# imp_match_v1_1.net
KiCad netlist of a schematic drawn in Altium Designer
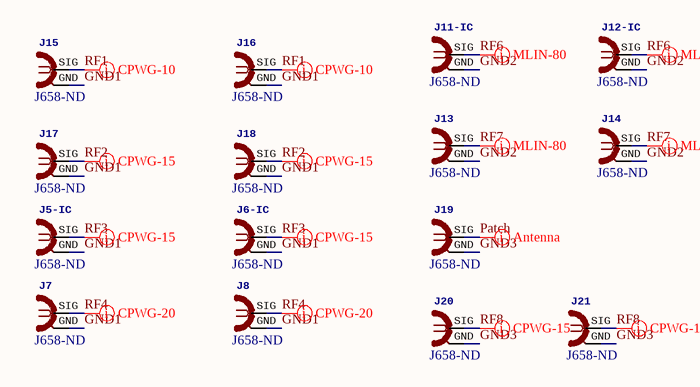
[diagram p0: imp_match_v1_1.SchDoc]

(export (version "E")
  (design (tool "Eeschema 10.0.6"))
  (components
    (comp (ref "J5-IC")
      (value "SMA 50 Ohm edge")
      (footprint "SMA-OSHPARK-4L-1.6MM- ALT3")
      (fields
        (field (name "SUPPLIER PART NUMBER 1") "J658-ND")
        (field (name "LIBRARYNAME") "dword1511-connectors")
      )
      (libsource (lib "wcsng_altium") (part "SMA-OSHPARK-4L-1.6MM-ALT3"))
    )
    (comp (ref "J6-IC")
      (value "SMA 50 Ohm edge")
      (footprint "SMA-OSHPARK-4L-1.6MM- ALT3")
      (fields
        (field (name "SUPPLIER PART NUMBER 1") "J658-ND")
        (field (name "LIBRARYNAME") "dword1511-connectors")
      )
      (libsource (lib "wcsng_altium") (part "SMA-OSHPARK-4L-1.6MM-ALT3"))
    )
    (comp (ref "J7")
      (value "SMA 50 Ohm edge")
      (footprint "SMA-OSHPARK-4L-1.6MM- ALT3")
      (fields
        (field (name "SUPPLIER PART NUMBER 1") "J658-ND")
        (field (name "LIBRARYNAME") "dword1511-connectors")
      )
      (libsource (lib "wcsng_altium") (part "SMA-OSHPARK-4L-1.6MM-ALT3"))
    )
    (comp (ref "J8")
      (value "SMA 50 Ohm edge")
      (footprint "SMA-OSHPARK-4L-1.6MM- ALT3")
      (fields
        (field (name "SUPPLIER PART NUMBER 1") "J658-ND")
        (field (name "LIBRARYNAME") "dword1511-connectors")
      )
      (libsource (lib "wcsng_altium") (part "SMA-OSHPARK-4L-1.6MM-ALT3"))
    )
    (comp (ref "J11-IC")
      (value "SMA 50 Ohm edge")
      (footprint "SMA-OSHPARK-4L-1.6MM- ALT3")
      (fields
        (field (name "SUPPLIER PART NUMBER 1") "J658-ND")
        (field (name "LIBRARYNAME") "dword1511-connectors")
      )
      (libsource (lib "wcsng_altium") (part "SMA-OSHPARK-4L-1.6MM-ALT3"))
    )
    (comp (ref "J12-IC")
      (value "SMA 50 Ohm edge")
      (footprint "SMA-OSHPARK-4L-1.6MM- ALT3")
      (fields
        (field (name "SUPPLIER PART NUMBER 1") "J658-ND")
        (field (name "LIBRARYNAME") "dword1511-connectors")
      )
      (libsource (lib "wcsng_altium") (part "SMA-OSHPARK-4L-1.6MM-ALT3"))
    )
    (comp (ref "J13")
      (value "SMA 50 Ohm edge")
      (footprint "SMA-OSHPARK-4L-1.6MM- ALT3")
      (fields
        (field (name "SUPPLIER PART NUMBER 1") "J658-ND")
        (field (name "LIBRARYNAME") "dword1511-connectors")
      )
      (libsource (lib "wcsng_altium") (part "SMA-OSHPARK-4L-1.6MM-ALT3"))
    )
    (comp (ref "J14")
      (value "SMA 50 Ohm edge")
      (footprint "SMA-OSHPARK-4L-1.6MM- ALT3")
      (fields
        (field (name "SUPPLIER PART NUMBER 1") "J658-ND")
        (field (name "LIBRARYNAME") "dword1511-connectors")
      )
      (libsource (lib "wcsng_altium") (part "SMA-OSHPARK-4L-1.6MM-ALT3"))
    )
    (comp (ref "J15")
      (value "SMA 50 Ohm edge")
      (footprint "SMA-OSHPARK-4L-1.6MM- ALT3")
      (fields
        (field (name "SUPPLIER PART NUMBER 1") "J658-ND")
        (field (name "LIBRARYNAME") "dword1511-connectors")
      )
      (libsource (lib "wcsng_altium") (part "SMA-OSHPARK-4L-1.6MM-ALT3"))
    )
    (comp (ref "J16")
      (value "SMA 50 Ohm edge")
      (footprint "SMA-OSHPARK-4L-1.6MM- ALT3")
      (fields
        (field (name "SUPPLIER PART NUMBER 1") "J658-ND")
        (field (name "LIBRARYNAME") "dword1511-connectors")
      )
      (libsource (lib "wcsng_altium") (part "SMA-OSHPARK-4L-1.6MM-ALT3"))
    )
    (comp (ref "J17")
      (value "SMA 50 Ohm edge")
      (footprint "SMA-OSHPARK-4L-1.6MM- ALT3")
      (fields
        (field (name "SUPPLIER PART NUMBER 1") "J658-ND")
        (field (name "LIBRARYNAME") "dword1511-connectors")
      )
      (libsource (lib "wcsng_altium") (part "SMA-OSHPARK-4L-1.6MM-ALT3"))
    )
    (comp (ref "J18")
      (value "SMA 50 Ohm edge")
      (footprint "SMA-OSHPARK-4L-1.6MM- ALT3")
      (fields
        (field (name "SUPPLIER PART NUMBER 1") "J658-ND")
        (field (name "LIBRARYNAME") "dword1511-connectors")
      )
      (libsource (lib "wcsng_altium") (part "SMA-OSHPARK-4L-1.6MM-ALT3"))
    )
    (comp (ref "J19")
      (value "SMA 50 Ohm edge")
      (footprint "SMA-OSHPARK-4L-1.6MM- ALT3")
      (fields
        (field (name "SUPPLIER PART NUMBER 1") "J658-ND")
        (field (name "LIBRARYNAME") "dword1511-connectors")
      )
      (libsource (lib "wcsng_altium") (part "SMA-OSHPARK-4L-1.6MM-ALT3"))
    )
    (comp (ref "J20")
      (value "SMA 50 Ohm edge")
      (footprint "SMA-OSHPARK-4L-1.6MM- ALT3")
      (fields
        (field (name "SUPPLIER PART NUMBER 1") "J658-ND")
        (field (name "LIBRARYNAME") "dword1511-connectors")
      )
      (libsource (lib "wcsng_altium") (part "SMA-OSHPARK-4L-1.6MM-ALT3"))
    )
    (comp (ref "J21")
      (value "SMA 50 Ohm edge")
      (footprint "SMA-OSHPARK-4L-1.6MM- ALT3")
      (fields
        (field (name "SUPPLIER PART NUMBER 1") "J658-ND")
        (field (name "LIBRARYNAME") "dword1511-connectors")
      )
      (libsource (lib "wcsng_altium") (part "SMA-OSHPARK-4L-1.6MM-ALT3"))
    )
  )
  (nets
    (net (code "1") (name "/GND1") (class "Default")
      (node (ref "J15") (pin "GND") (pinfunction "GND_GND") (pintype "passive"))
      (node (ref "J16") (pin "GND") (pinfunction "GND_GND") (pintype "passive"))
      (node (ref "J17") (pin "GND") (pinfunction "GND_GND") (pintype "passive"))
      (node (ref "J18") (pin "GND") (pinfunction "GND_GND") (pintype "passive"))
      (node (ref "J5-IC") (pin "GND") (pinfunction "GND_GND") (pintype "passive"))
      (node (ref "J6-IC") (pin "GND") (pinfunction "GND_GND") (pintype "passive"))
      (node (ref "J7") (pin "GND") (pinfunction "GND_GND") (pintype "passive"))
      (node (ref "J8") (pin "GND") (pinfunction "GND_GND") (pintype "passive"))
    )
    (net (code "2") (name "/GND2") (class "Default")
      (node (ref "J11-IC") (pin "GND") (pinfunction "GND_GND") (pintype "passive"))
      (node (ref "J12-IC") (pin "GND") (pinfunction "GND_GND") (pintype "passive"))
      (node (ref "J13") (pin "GND") (pinfunction "GND_GND") (pintype "passive"))
      (node (ref "J14") (pin "GND") (pinfunction "GND_GND") (pintype "passive"))
    )
    (net (code "3") (name "/GND3") (class "Default")
      (node (ref "J19") (pin "GND") (pinfunction "GND_GND") (pintype "passive"))
      (node (ref "J20") (pin "GND") (pinfunction "GND_GND") (pintype "passive"))
      (node (ref "J21") (pin "GND") (pinfunction "GND_GND") (pintype "passive"))
    )
    (net (code "4") (name "/Patch") (class "Default")
      (node (ref "J19") (pin "SIG") (pinfunction "SIG_SIG") (pintype "passive"))
    )
    (net (code "5") (name "/RF1") (class "Default")
      (node (ref "J15") (pin "SIG") (pinfunction "SIG_SIG") (pintype "passive"))
      (node (ref "J16") (pin "SIG") (pinfunction "SIG_SIG") (pintype "passive"))
    )
    (net (code "6") (name "/RF2") (class "Default")
      (node (ref "J17") (pin "SIG") (pinfunction "SIG_SIG") (pintype "passive"))
      (node (ref "J18") (pin "SIG") (pinfunction "SIG_SIG") (pintype "passive"))
    )
    (net (code "7") (name "/RF3") (class "Default")
      (node (ref "J5-IC") (pin "SIG") (pinfunction "SIG_SIG") (pintype "passive"))
      (node (ref "J6-IC") (pin "SIG") (pinfunction "SIG_SIG") (pintype "passive"))
    )
    (net (code "8") (name "/RF4") (class "Default")
      (node (ref "J7") (pin "SIG") (pinfunction "SIG_SIG") (pintype "passive"))
      (node (ref "J8") (pin "SIG") (pinfunction "SIG_SIG") (pintype "passive"))
    )
    (net (code "9") (name "/RF6") (class "Default")
      (node (ref "J11-IC") (pin "SIG") (pinfunction "SIG_SIG") (pintype "passive"))
      (node (ref "J12-IC") (pin "SIG") (pinfunction "SIG_SIG") (pintype "passive"))
    )
    (net (code "10") (name "/RF7") (class "Default")
      (node (ref "J13") (pin "SIG") (pinfunction "SIG_SIG") (pintype "passive"))
      (node (ref "J14") (pin "SIG") (pinfunction "SIG_SIG") (pintype "passive"))
    )
    (net (code "11") (name "/RF8") (class "Default")
      (node (ref "J20") (pin "SIG") (pinfunction "SIG_SIG") (pintype "passive"))
      (node (ref "J21") (pin "SIG") (pinfunction "SIG_SIG") (pintype "passive"))
    )
  )
)
